# Candunio.net
KiCad netlist of a schematic drawn in Altium Designer
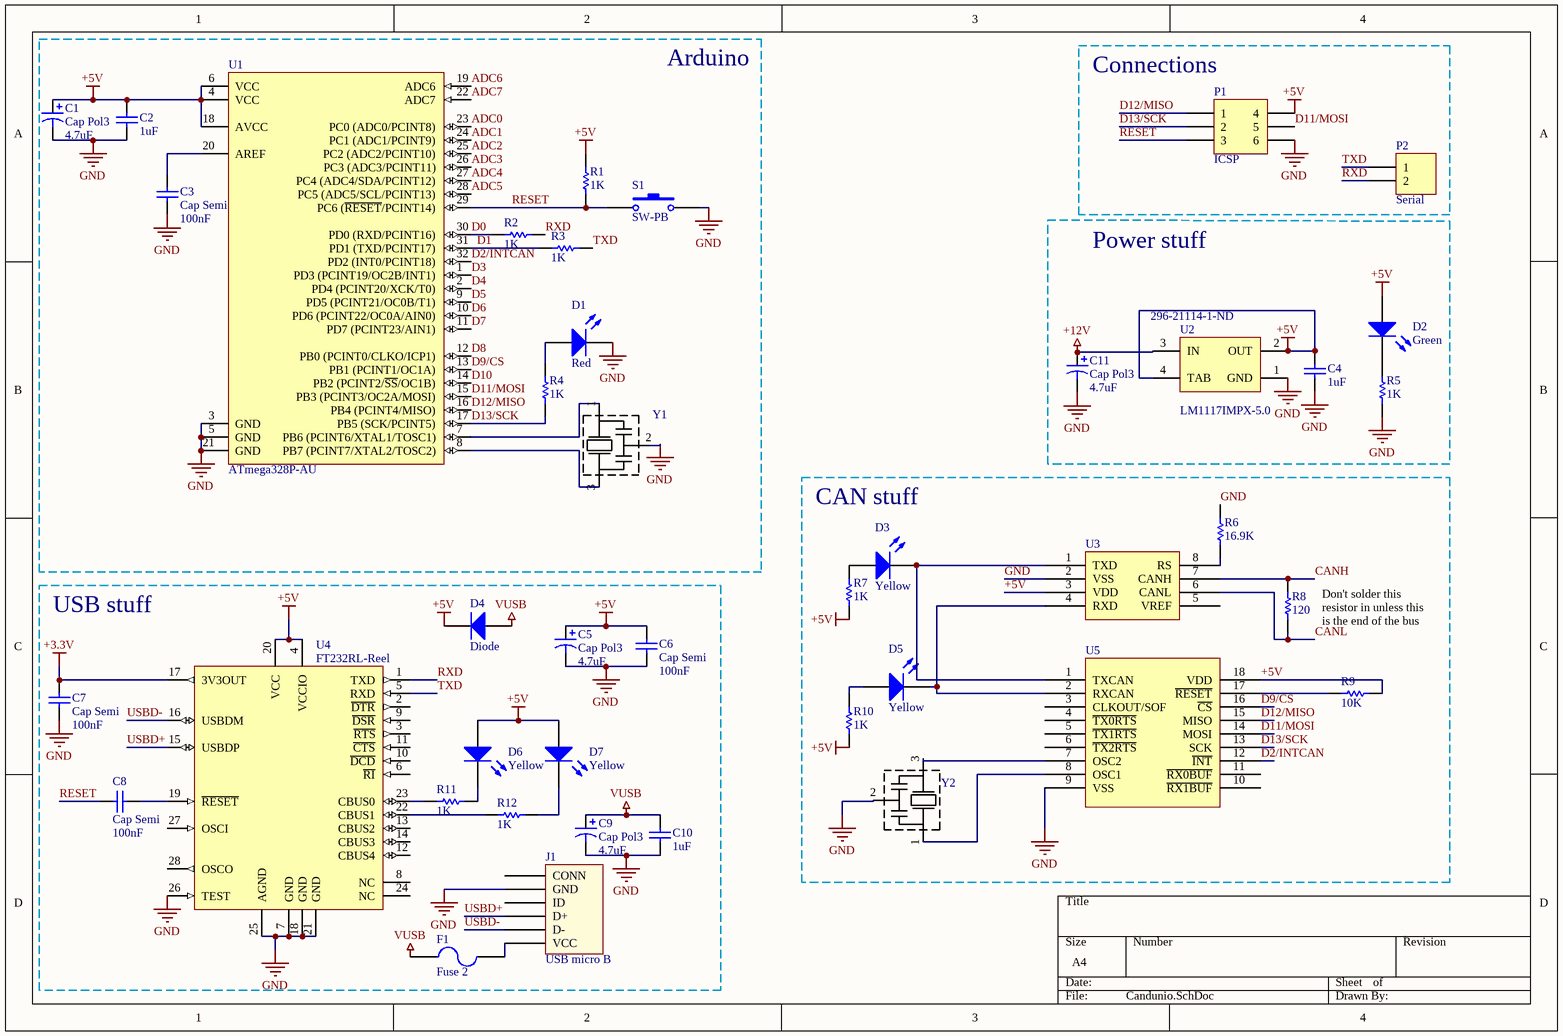
[diagram p0: Candunio.SchDoc]

(export (version "E")
  (design (tool "Eeschema 10.0.6"))
  (components
    (comp (ref "C1")
      (value "Cap Pol3")
      (footprint "C1206")
      (description "Polarized Capacitor (Surface Mount)")
      (fields
        (field (name "ALTIUM_VALUE") "4.7uF")
        (field (name "MANUFACTURER") "Kyocera AVX")
        (field (name "MANUFACTURER PART NUMBER") "12063C475KAT2A")
        (field (name "PUBLISHER") "Altium Limited")
      )
      (libsource (lib "Miscellaneous Devices") (part "Cap Pol3"))
    )
    (comp (ref "C2")
      (value "1uF")
      (footprint "C1206")
      (description "Capacitor (Semiconductor SIM Model)")
      (fields
        (field (name "MANUFACTURER") "Murata")
        (field (name "MANUFACTURER PART NUMBER") "GRM31MR71H105KA88L")
        (field (name "PUBLISHER") "Altium Limited")
      )
      (libsource (lib "Miscellaneous Devices") (part "Cap Semi"))
    )
    (comp (ref "C3")
      (value "Cap Semi")
      (footprint "C1206")
      (description "Capacitor (Semiconductor SIM Model)")
      (fields
        (field (name "ALTIUM_VALUE") "100nF")
        (field (name "MANUFACTURER") "Yageo")
        (field (name "MANUFACTURER PART NUMBER") "CC1206KKX7R0BB104")
        (field (name "PUBLISHER") "Altium Limited")
      )
      (libsource (lib "Miscellaneous Devices") (part "Cap Semi"))
    )
    (comp (ref "C4")
      (value "1uF")
      (footprint "C1206")
      (description "Capacitor (Semiconductor SIM Model)")
      (fields
        (field (name "MANUFACTURER") "Murata")
        (field (name "MANUFACTURER PART NUMBER") "GRM31MR71H105KA88L")
        (field (name "PUBLISHER") "Altium Limited")
      )
      (libsource (lib "Miscellaneous Devices") (part "Cap Semi"))
    )
    (comp (ref "C5")
      (value "Cap Pol3")
      (footprint "C1206")
      (description "Polarized Capacitor (Surface Mount)")
      (fields
        (field (name "ALTIUM_VALUE") "4.7uF")
        (field (name "MANUFACTURER") "Kyocera AVX")
        (field (name "MANUFACTURER PART NUMBER") "12063C475KAT2A")
        (field (name "PUBLISHER") "Altium Limited")
      )
      (libsource (lib "Miscellaneous Devices") (part "Cap Pol3"))
    )
    (comp (ref "C6")
      (value "Cap Semi")
      (footprint "C1206")
      (description "Capacitor (Semiconductor SIM Model)")
      (fields
        (field (name "ALTIUM_VALUE") "100nF")
        (field (name "MANUFACTURER") "Yageo")
        (field (name "MANUFACTURER PART NUMBER") "CC1206KKX7R0BB104")
        (field (name "PUBLISHER") "Altium Limited")
      )
      (libsource (lib "Miscellaneous Devices") (part "Cap Semi"))
    )
    (comp (ref "C7")
      (value "Cap Semi")
      (footprint "C1206")
      (description "Capacitor (Semiconductor SIM Model)")
      (fields
        (field (name "ALTIUM_VALUE") "100nF")
        (field (name "MANUFACTURER") "Yageo")
        (field (name "MANUFACTURER PART NUMBER") "CC1206KKX7R0BB104")
        (field (name "PUBLISHER") "Altium Limited")
      )
      (libsource (lib "Miscellaneous Devices") (part "Cap Semi"))
    )
    (comp (ref "C8")
      (value "Cap Semi")
      (footprint "C1206")
      (description "Capacitor (Semiconductor SIM Model)")
      (fields
        (field (name "ALTIUM_VALUE") "100nF")
        (field (name "MANUFACTURER") "Yageo")
        (field (name "MANUFACTURER PART NUMBER") "CC1206KKX7R0BB104")
        (field (name "PUBLISHER") "Altium Limited")
      )
      (libsource (lib "Miscellaneous Devices") (part "Cap Semi"))
    )
    (comp (ref "C9")
      (value "Cap Pol3")
      (footprint "C1206")
      (description "Polarized Capacitor (Surface Mount)")
      (fields
        (field (name "ALTIUM_VALUE") "4.7uF")
        (field (name "MANUFACTURER") "Kyocera AVX")
        (field (name "MANUFACTURER PART NUMBER") "12063C475KAT2A")
        (field (name "PUBLISHER") "Altium Limited")
      )
      (libsource (lib "Miscellaneous Devices") (part "Cap Pol3"))
    )
    (comp (ref "C10")
      (value "1uF")
      (footprint "C1206")
      (description "Capacitor (Semiconductor SIM Model)")
      (fields
        (field (name "MANUFACTURER") "Murata")
        (field (name "MANUFACTURER PART NUMBER") "GRM31MR71H105KA88L")
        (field (name "PUBLISHER") "Altium Limited")
      )
      (libsource (lib "Miscellaneous Devices") (part "Cap Semi"))
    )
    (comp (ref "C11")
      (value "Cap Pol3")
      (footprint "C1206")
      (description "Polarized Capacitor (Surface Mount)")
      (fields
        (field (name "ALTIUM_VALUE") "4.7uF")
        (field (name "MANUFACTURER") "Kyocera AVX")
        (field (name "MANUFACTURER PART NUMBER") "12063C475KAT2A")
        (field (name "PUBLISHER") "Altium Limited")
      )
      (libsource (lib "Miscellaneous Devices") (part "Cap Pol3"))
    )
    (comp (ref "D1")
      (value "Red")
      (footprint "3.2X1.6X1.1")
      (description "Typical RED, GREEN, YELLOW, AMBER GaAs LED")
      (fields
        (field (name "MANUFACTURER") "Broadcom Avago")
        (field (name "MANUFACTURER PART NUMBER") "HSMY-C150")
        (field (name "PUBLISHER") "Altium Limited")
      )
      (libsource (lib "Miscellaneous Devices") (part "LED2"))
    )
    (comp (ref "D2")
      (value "Green")
      (footprint "3.2X1.6X1.1")
      (description "Typical RED, GREEN, YELLOW, AMBER GaAs LED")
      (fields
        (field (name "MANUFACTURER") "Broadcom Avago")
        (field (name "MANUFACTURER PART NUMBER") "HSMG-C150")
        (field (name "PUBLISHER") "Altium Limited")
      )
      (libsource (lib "Miscellaneous Devices") (part "LED2"))
    )
    (comp (ref "D3")
      (value "Yellow")
      (footprint "3.2X1.6X1.1")
      (description "Typical RED, GREEN, YELLOW, AMBER GaAs LED")
      (fields
        (field (name "MANUFACTURER") "Broadcom Avago")
        (field (name "MANUFACTURER PART NUMBER") "HSMY-C150")
        (field (name "PUBLISHER") "Altium Limited")
      )
      (libsource (lib "Miscellaneous Devices") (part "LED2"))
    )
    (comp (ref "D4")
      (value "Diode")
      (footprint "SMC")
      (description "Default Diode")
      (fields (field (name "PUBLISHER") "Altium Limited"))
      (libsource (lib "Miscellaneous Devices") (part "Diode"))
    )
    (comp (ref "D5")
      (value "Yellow")
      (footprint "3.2X1.6X1.1")
      (description "Typical RED, GREEN, YELLOW, AMBER GaAs LED")
      (fields
        (field (name "MANUFACTURER") "Broadcom Avago")
        (field (name "MANUFACTURER PART NUMBER") "HSMY-C150")
        (field (name "PUBLISHER") "Altium Limited")
      )
      (libsource (lib "Miscellaneous Devices") (part "LED2"))
    )
    (comp (ref "D6")
      (value "Yellow")
      (footprint "3.2X1.6X1.1")
      (description "Typical RED, GREEN, YELLOW, AMBER GaAs LED")
      (fields
        (field (name "MANUFACTURER") "Broadcom Avago")
        (field (name "MANUFACTURER PART NUMBER") "HSMY-C150")
        (field (name "PUBLISHER") "Altium Limited")
      )
      (libsource (lib "Miscellaneous Devices") (part "LED2"))
    )
    (comp (ref "D7")
      (value "Yellow")
      (footprint "3.2X1.6X1.1")
      (description "Typical RED, GREEN, YELLOW, AMBER GaAs LED")
      (fields
        (field (name "MANUFACTURER") "Broadcom Avago")
        (field (name "MANUFACTURER PART NUMBER") "HSMY-C150")
        (field (name "PUBLISHER") "Altium Limited")
      )
      (libsource (lib "Miscellaneous Devices") (part "LED2"))
    )
    (comp (ref "F1")
      (value "Fuse 2")
      (footprint "1812")
      (description "Fuse")
      (fields
        (field (name "PART NUMBER") "MF-MSMF050-2")
        (field (name "MANUFACTURER") "Bourns")
        (field (name "PUBLISHER") "Altium Limited")
      )
      (libsource (lib "Miscellaneous Devices") (part "Fuse 2"))
    )
    (comp (ref "J1")
      (value "USB micro B")
      (footprint "1050170001")
      (description "CONN SM TH USB MICRO MODIFIED FOR DRILL")
      (fields (field (name "PART NUMBER") "WM1399CT-ND"))
      (libsource (lib "electronpowered") (part "1050170001"))
    )
    (comp (ref "P1")
      (value "ICSP")
      (footprint "HDR2X3_CEN")
      (description "Header, 3-Pin, Dual row")
      (fields (field (name "PUBLISHER") "Altium Limited"))
      (libsource (lib "Miscellaneous Connectors") (part "Header 3X2A"))
    )
    (comp (ref "P2")
      (value "Serial")
      (footprint "HDR1X2")
      (description "Header, 2-Pin")
      (fields (field (name "PUBLISHER") "Altium Limited"))
      (libsource (lib "Miscellaneous Connectors") (part "Header 2"))
    )
    (comp (ref "R1")
      (value "1K")
      (footprint "C1206")
      (description "Resistor")
      (fields
        (field (name "MANUFACTURER") "Stackpole Electronics")
        (field (name "MANUFACTURER PART NUMBER") "RNCP1206FTD1K00")
      )
      (libsource (lib "Miscellaneous Devices") (part "Res1"))
    )
    (comp (ref "R2")
      (value "1K")
      (footprint "C1206")
      (description "Resistor")
      (fields
        (field (name "MANUFACTURER") "Stackpole Electronics")
        (field (name "MANUFACTURER PART NUMBER") "RNCP1206FTD1K00")
      )
      (libsource (lib "Miscellaneous Devices") (part "Res1"))
    )
    (comp (ref "R3")
      (value "1K")
      (footprint "C1206")
      (description "Resistor")
      (fields
        (field (name "MANUFACTURER") "Stackpole Electronics")
        (field (name "MANUFACTURER PART NUMBER") "RNCP1206FTD1K00")
      )
      (libsource (lib "Miscellaneous Devices") (part "Res1"))
    )
    (comp (ref "R4")
      (value "1K")
      (footprint "C1206")
      (description "Resistor")
      (fields
        (field (name "MANUFACTURER") "Stackpole Electronics")
        (field (name "MANUFACTURER PART NUMBER") "RNCP1206FTD1K00")
      )
      (libsource (lib "Miscellaneous Devices") (part "Res1"))
    )
    (comp (ref "R5")
      (value "1K")
      (footprint "C1206")
      (description "Resistor")
      (fields
        (field (name "MANUFACTURER") "Stackpole Electronics")
        (field (name "MANUFACTURER PART NUMBER") "RNCP1206FTD1K00")
      )
      (libsource (lib "Miscellaneous Devices") (part "Res1"))
    )
    (comp (ref "R6")
      (value "16.9K")
      (footprint "C1206")
      (description "Resistor")
      (fields
        (field (name "MANUFACTURER") "TE Connectivity Holsworthy")
        (field (name "MANUFACTURER PART NUMBER") "CRGH1206F16K9")
      )
      (libsource (lib "Miscellaneous Devices") (part "Res1"))
    )
    (comp (ref "R7")
      (value "1K")
      (footprint "C1206")
      (description "Resistor")
      (fields
        (field (name "MANUFACTURER") "Stackpole Electronics")
        (field (name "MANUFACTURER PART NUMBER") "RNCP1206FTD1K00")
      )
      (libsource (lib "Miscellaneous Devices") (part "Res1"))
    )
    (comp (ref "R8")
      (value "120")
      (footprint "C1206")
      (description "Resistor")
      (fields
        (field (name "MANUFACTURER") "Vishay")
        (field (name "MANUFACTURER PART NUMBER") "CRCW1206120RFKEAHP")
      )
      (libsource (lib "Miscellaneous Devices") (part "Res1"))
    )
    (comp (ref "R9")
      (value "10K")
      (footprint "C1206")
      (description "Resistor")
      (fields
        (field (name "MANUFACTURER") "Stackpole Electronics")
        (field (name "MANUFACTURER PART NUMBER") "RNCP1206FTD10K0")
      )
      (libsource (lib "Miscellaneous Devices") (part "Res1"))
    )
    (comp (ref "R10")
      (value "1K")
      (footprint "C1206")
      (description "Resistor")
      (fields
        (field (name "MANUFACTURER") "Stackpole Electronics")
        (field (name "MANUFACTURER PART NUMBER") "RNCP1206FTD1K00")
      )
      (libsource (lib "Miscellaneous Devices") (part "Res1"))
    )
    (comp (ref "R11")
      (value "1K")
      (footprint "C1206")
      (description "Resistor")
      (fields
        (field (name "MANUFACTURER") "Stackpole Electronics")
        (field (name "MANUFACTURER PART NUMBER") "RNCP1206FTD1K00")
      )
      (libsource (lib "Miscellaneous Devices") (part "Res1"))
    )
    (comp (ref "R12")
      (value "1K")
      (footprint "C1206")
      (description "Resistor")
      (fields
        (field (name "MANUFACTURER") "Stackpole Electronics")
        (field (name "MANUFACTURER PART NUMBER") "RNCP1206FTD1K00")
      )
      (libsource (lib "Miscellaneous Devices") (part "Res1"))
    )
    (comp (ref "S1")
      (value "SW-PB")
      (footprint "C1206")
      (description "Switch")
      (fields
        (field (name "MANUFACTURER") "ITT C&K")
        (field (name "MANUFACTURER PART NUMBER") "KXT331LHS")
        (field (name "PUBLISHER") "Altium Limited")
      )
      (libsource (lib "Miscellaneous Devices") (part "SW-PB"))
    )
    (comp (ref "U1")
      (value "ATmega328P-AU")
      (footprint "32A_N")
      (fields (field (name "PUBLISHER") "Altium Limited"))
      (libsource (lib "Atmel Microcontroller 8-Bit megaAVR") (part "ATmega328P-AU"))
    )
    (comp (ref "U2")
      (value "LM1117IMPX-5.0")
      (footprint "MP04A_N")
      (description "800mA Low-Dropout Linear Regulator, 4-pin SOT-223")
      (fields
        (field (name "PARTNUMBER") "LM1117IMPX-5.0/NOPBCT-ND")
        (field (name "MANUFACTURER") "National Semiconductor")
        (field (name "SUPPLIER PART NUMBER") "296-21114-1-ND")
        (field (name "PUBLISHER") "Altium Limited")
      )
      (libsource (lib "NSC LDO") (part "LM1117IMPX-5.0"))
    )
    (comp (ref "U3")
      (value "MCP2551-E/SN")
      (footprint "SOIC127P600X175-8M")
      (description "SOIC")
      (libsource (lib "AMSComponents") (part "MCP2551-E/SN"))
    )
    (comp (ref "U4")
      (value "FT232RL-Reel")
      (footprint "SSOP-28_N")
      (description "USB UART Asynchronous Serial Data Transfer Chip, SSOP-28, Tape and Reel")
      (fields
        (field (name "MANUFACTURER") "FTDI")
        (field (name "MANUFACTURER PART NUMBER") "FT232RL-REEL")
        (field (name "PUBLISHER") "Altium Limited")
      )
      (libsource (lib "FTDI Communication UART") (part "FT232RL-Reel"))
    )
    (comp (ref "U5")
      (value "MCP2515-E/ST")
      (footprint "SOIC127P1030X265-18M")
      (description "SOIC")
      (libsource (lib "AMSComponents") (part "MCP2515-E/ST"))
    )
    (comp (ref "Y1")
      (value "CSTCE16M0V53-R0")
      (footprint "CSTCE16M0V53-R0")
      (fields
        (field (name "MANUFACTURER") "Murata")
        (field (name "MANUFACTURER PART NUMBER") "CSTCE16M0V53C-R0")
        (field (name "TOLERANCE") "0.5%")
      )
      (libsource (lib "AMSComponents") (part "CSTCE16M0V53-R0"))
    )
    (comp (ref "Y2")
      (value "CSTCE16M0V53-R0")
      (footprint "CSTCE16M0V53-R0")
      (fields
        (field (name "MANUFACTURER") "Murata")
        (field (name "MANUFACTURER PART NUMBER") "CSTCE16M0V53C-R0")
        (field (name "TOLERANCE") "0.5%")
      )
      (libsource (lib "AMSComponents") (part "CSTCE16M0V53-R0"))
    )
  )
  (nets
    (net (code "1") (name "+3.3V") (class "Default")
      (node (ref "C7") (pin "1") (pinfunction "1_1") (pintype "passive"))
      (node (ref "U4") (pin "17") (pinfunction "3V3OUT_17") (pintype "output"))
    )
    (net (code "2") (name "+5V") (class "Default")
      (node (ref "C1") (pin "1") (pinfunction "1_1") (pintype "passive"))
      (node (ref "C2") (pin "1") (pinfunction "1_1") (pintype "passive"))
      (node (ref "C4") (pin "1") (pinfunction "1_1") (pintype "passive"))
      (node (ref "C5") (pin "1") (pinfunction "1_1") (pintype "passive"))
      (node (ref "C6") (pin "1") (pinfunction "1_1") (pintype "passive"))
      (node (ref "D2") (pin "1") (pinfunction "A_1") (pintype "passive"))
      (node (ref "D4") (pin "2") (pinfunction "K_2") (pintype "passive"))
      (node (ref "D6") (pin "1") (pinfunction "A_1") (pintype "passive"))
      (node (ref "D7") (pin "1") (pinfunction "A_1") (pintype "passive"))
      (node (ref "P1") (pin "4") (pinfunction "4_4") (pintype "passive"))
      (node (ref "R1") (pin "1") (pinfunction "1_1") (pintype "passive"))
      (node (ref "R10") (pin "2") (pinfunction "2_2") (pintype "passive"))
      (node (ref "R7") (pin "1") (pinfunction "1_1") (pintype "passive"))
      (node (ref "R9") (pin "2") (pinfunction "2_2") (pintype "passive"))
      (node (ref "U1") (pin "18") (pinfunction "AVCC_18") (pintype "power_in"))
      (node (ref "U1") (pin "4") (pinfunction "VCC_4") (pintype "power_in"))
      (node (ref "U1") (pin "6") (pinfunction "VCC_6") (pintype "power_in"))
      (node (ref "U2") (pin "2") (pinfunction "OUT_2") (pintype "power_in"))
      (node (ref "U2") (pin "4") (pinfunction "TAB_4") (pintype "power_in"))
      (node (ref "U3") (pin "3") (pinfunction "VDD_3") (pintype "passive"))
      (node (ref "U4") (pin "20") (pinfunction "VCC_20") (pintype "power_in"))
      (node (ref "U4") (pin "4") (pinfunction "VCCIO_4") (pintype "power_in"))
      (node (ref "U5") (pin "18") (pinfunction "VDD_18") (pintype "passive"))
    )
    (net (code "3") (name "+12V") (class "Default")
      (node (ref "C11") (pin "1") (pinfunction "1_1") (pintype "passive"))
      (node (ref "U2") (pin "3") (pinfunction "IN_3") (pintype "power_in"))
    )
    (net (code "4") (name "/ADC0") (class "Default")
      (node (ref "U1") (pin "23") (pinfunction "PC0_(ADC0/PCINT8)_23") (pintype "bidirectional"))
    )
    (net (code "5") (name "/ADC1") (class "Default")
      (node (ref "U1") (pin "24") (pinfunction "PC1_(ADC1/PCINT9)_24") (pintype "bidirectional"))
    )
    (net (code "6") (name "/ADC2") (class "Default")
      (node (ref "U1") (pin "25") (pinfunction "PC2_(ADC2/PCINT10)_25") (pintype "bidirectional"))
    )
    (net (code "7") (name "/ADC3") (class "Default")
      (node (ref "U1") (pin "26") (pinfunction "PC3_(ADC3/PCINT11)_26") (pintype "bidirectional"))
    )
    (net (code "8") (name "/ADC4") (class "Default")
      (node (ref "U1") (pin "27") (pinfunction "PC4_(ADC4/SDA/PCINT12)_27") (pintype "bidirectional"))
    )
    (net (code "9") (name "/ADC5") (class "Default")
      (node (ref "U1") (pin "28") (pinfunction "PC5_(ADC5/SCL/PCINT13)_28") (pintype "bidirectional"))
    )
    (net (code "10") (name "/ADC6") (class "Default")
      (node (ref "U1") (pin "19") (pinfunction "ADC6_19") (pintype "input"))
    )
    (net (code "11") (name "/ADC7") (class "Default")
      (node (ref "U1") (pin "22") (pinfunction "ADC7_22") (pintype "input"))
    )
    (net (code "12") (name "/CANH") (class "Default")
      (node (ref "R8") (pin "1") (pinfunction "1_1") (pintype "passive"))
      (node (ref "U3") (pin "7") (pinfunction "CANH_7") (pintype "passive"))
    )
    (net (code "13") (name "/CANL") (class "Default")
      (node (ref "R8") (pin "2") (pinfunction "2_2") (pintype "passive"))
      (node (ref "U3") (pin "6") (pinfunction "CANL_6") (pintype "passive"))
    )
    (net (code "14") (name "/D0") (class "Default")
      (node (ref "R2") (pin "1") (pinfunction "1_1") (pintype "passive"))
      (node (ref "U1") (pin "30") (pinfunction "PD0_(RXD/PCINT16)_30") (pintype "bidirectional"))
    )
    (net (code "15") (name "/D1") (class "Default")
      (node (ref "R3") (pin "1") (pinfunction "1_1") (pintype "passive"))
      (node (ref "U1") (pin "31") (pinfunction "PD1_(TXD/PCINT17)_31") (pintype "bidirectional"))
    )
    (net (code "16") (name "/D2{slash}INTCAN") (class "Default")
      (node (ref "U1") (pin "32") (pinfunction "PD2_(INT0/PCINT18)_32") (pintype "bidirectional"))
      (node (ref "U5") (pin "12") (pinfunction "~{INT}_12") (pintype "passive"))
    )
    (net (code "17") (name "/D3") (class "Default")
      (node (ref "U1") (pin "1") (pinfunction "PD3_(PCINT19/OC2B/INT1)_1") (pintype "bidirectional"))
    )
    (net (code "18") (name "/D4") (class "Default")
      (node (ref "U1") (pin "2") (pinfunction "PD4_(PCINT20/XCK/T0)_2") (pintype "bidirectional"))
    )
    (net (code "19") (name "/D5") (class "Default")
      (node (ref "U1") (pin "9") (pinfunction "PD5_(PCINT21/OC0B/T1)_9") (pintype "bidirectional"))
    )
    (net (code "20") (name "/D6") (class "Default")
      (node (ref "U1") (pin "10") (pinfunction "PD6_(PCINT22/OC0A/AIN0)_10") (pintype "bidirectional"))
    )
    (net (code "21") (name "/D7") (class "Default")
      (node (ref "U1") (pin "11") (pinfunction "PD7_(PCINT23/AIN1)_11") (pintype "bidirectional"))
    )
    (net (code "22") (name "/D8") (class "Default")
      (node (ref "U1") (pin "12") (pinfunction "PB0_(PCINT0/CLKO/ICP1)_12") (pintype "bidirectional"))
    )
    (net (code "23") (name "/D9{slash}CS") (class "Default")
      (node (ref "U1") (pin "13") (pinfunction "PB1_(PCINT1/OC1A)_13") (pintype "bidirectional"))
      (node (ref "U5") (pin "16") (pinfunction "~{CS}_16") (pintype "passive"))
    )
    (net (code "24") (name "/D10") (class "Default")
      (node (ref "U1") (pin "14") (pinfunction "PB2_(PCINT2/~{SS}/OC1B)_14") (pintype "bidirectional"))
    )
    (net (code "25") (name "/D11{slash}MOSI") (class "Default")
      (node (ref "P1") (pin "5") (pinfunction "5_5") (pintype "passive"))
      (node (ref "U1") (pin "15") (pinfunction "PB3_(PCINT3/OC2A/MOSI)_15") (pintype "bidirectional"))
      (node (ref "U5") (pin "14") (pinfunction "MOSI_14") (pintype "passive"))
    )
    (net (code "26") (name "/D12{slash}MISO") (class "Default")
      (node (ref "P1") (pin "1") (pinfunction "1_1") (pintype "passive"))
      (node (ref "U1") (pin "16") (pinfunction "PB4_(PCINT4/MISO)_16") (pintype "bidirectional"))
      (node (ref "U5") (pin "15") (pinfunction "MISO_15") (pintype "passive"))
    )
    (net (code "27") (name "/D13{slash}SCK") (class "Default")
      (node (ref "P1") (pin "2") (pinfunction "2_2") (pintype "passive"))
      (node (ref "R4") (pin "2") (pinfunction "2_2") (pintype "passive"))
      (node (ref "U1") (pin "17") (pinfunction "PB5_(SCK/PCINT5)_17") (pintype "bidirectional"))
      (node (ref "U5") (pin "13") (pinfunction "SCK_13") (pintype "passive"))
    )
    (net (code "28") (name "/RESET") (class "Default")
      (node (ref "C8") (pin "1") (pinfunction "1_1") (pintype "passive"))
      (node (ref "P1") (pin "3") (pinfunction "3_3") (pintype "passive"))
      (node (ref "R1") (pin "2") (pinfunction "2_2") (pintype "passive"))
      (node (ref "S1") (pin "1") (pinfunction "1_1") (pintype "passive"))
      (node (ref "U1") (pin "29") (pinfunction "PC6_(~{RESET}/PCINT14)_29") (pintype "bidirectional"))
    )
    (net (code "29") (name "/RXD") (class "Default")
      (node (ref "P2") (pin "2") (pinfunction "2_2") (pintype "passive"))
      (node (ref "R2") (pin "2") (pinfunction "2_2") (pintype "passive"))
      (node (ref "U4") (pin "1") (pinfunction "TXD_1") (pintype "output"))
    )
    (net (code "30") (name "/TXD") (class "Default")
      (node (ref "P2") (pin "1") (pinfunction "1_1") (pintype "passive"))
      (node (ref "R3") (pin "2") (pinfunction "2_2") (pintype "passive"))
      (node (ref "U4") (pin "5") (pinfunction "RXD_5") (pintype "input"))
    )
    (net (code "31") (name "/USBD+") (class "Default")
      (node (ref "J1") (pin "3") (pinfunction "D+_3") (pintype "passive"))
      (node (ref "U4") (pin "15") (pinfunction "USBDP_15") (pintype "bidirectional"))
    )
    (net (code "32") (name "/USBD-") (class "Default")
      (node (ref "J1") (pin "2") (pinfunction "D-_2") (pintype "passive"))
      (node (ref "U4") (pin "16") (pinfunction "USBDM_16") (pintype "bidirectional"))
    )
    (net (code "33") (name "GND") (class "Default")
      (node (ref "C1") (pin "2") (pinfunction "2_2") (pintype "passive"))
      (node (ref "C10") (pin "2") (pinfunction "2_2") (pintype "passive"))
      (node (ref "C11") (pin "2") (pinfunction "2_2") (pintype "passive"))
      (node (ref "C2") (pin "2") (pinfunction "2_2") (pintype "passive"))
      (node (ref "C3") (pin "2") (pinfunction "2_2") (pintype "passive"))
      (node (ref "C4") (pin "2") (pinfunction "2_2") (pintype "passive"))
      (node (ref "C5") (pin "2") (pinfunction "2_2") (pintype "passive"))
      (node (ref "C6") (pin "2") (pinfunction "2_2") (pintype "passive"))
      (node (ref "C7") (pin "2") (pinfunction "2_2") (pintype "passive"))
      (node (ref "C9") (pin "2") (pinfunction "2_2") (pintype "passive"))
      (node (ref "D1") (pin "2") (pinfunction "K_2") (pintype "passive"))
      (node (ref "J1") (pin "5") (pinfunction "GND_5") (pintype "passive"))
      (node (ref "P1") (pin "6") (pinfunction "6_6") (pintype "passive"))
      (node (ref "R5") (pin "2") (pinfunction "2_2") (pintype "passive"))
      (node (ref "R6") (pin "1") (pinfunction "1_1") (pintype "passive"))
      (node (ref "S1") (pin "2") (pinfunction "2_2") (pintype "passive"))
      (node (ref "U1") (pin "21") (pinfunction "GND_21") (pintype "power_in"))
      (node (ref "U1") (pin "3") (pinfunction "GND_3") (pintype "power_in"))
      (node (ref "U1") (pin "5") (pinfunction "GND_5") (pintype "power_in"))
      (node (ref "U2") (pin "1") (pinfunction "GND_1") (pintype "power_in"))
      (node (ref "U3") (pin "2") (pinfunction "VSS_2") (pintype "passive"))
      (node (ref "U4") (pin "18") (pinfunction "GND_18") (pintype "power_in"))
      (node (ref "U4") (pin "21") (pinfunction "GND_21") (pintype "power_in"))
      (node (ref "U4") (pin "25") (pinfunction "AGND_25") (pintype "power_in"))
      (node (ref "U4") (pin "26") (pinfunction "TEST_26") (pintype "input"))
      (node (ref "U4") (pin "7") (pinfunction "GND_7") (pintype "power_in"))
      (node (ref "U5") (pin "9") (pinfunction "VSS_9") (pintype "passive"))
      (node (ref "Y1") (pin "2") (pinfunction "2_2") (pintype "passive"))
      (node (ref "Y2") (pin "2") (pinfunction "2_2") (pintype "passive"))
    )
    (net (code "34") (name "Net-(D1-A)") (class "Default")
      (node (ref "D1") (pin "1") (pinfunction "A_1") (pintype "passive"))
      (node (ref "R4") (pin "1") (pinfunction "1_1") (pintype "passive"))
    )
    (net (code "35") (name "Net-(D2-K)") (class "Default")
      (node (ref "D2") (pin "2") (pinfunction "K_2") (pintype "passive"))
      (node (ref "R5") (pin "1") (pinfunction "1_1") (pintype "passive"))
    )
    (net (code "36") (name "Net-(D3-A)") (class "Default")
      (node (ref "D3") (pin "1") (pinfunction "A_1") (pintype "passive"))
      (node (ref "R7") (pin "2") (pinfunction "2_2") (pintype "passive"))
    )
    (net (code "37") (name "Net-(D3-K)") (class "Default")
      (node (ref "D3") (pin "2") (pinfunction "K_2") (pintype "passive"))
      (node (ref "U3") (pin "1") (pinfunction "TXD_1") (pintype "passive"))
      (node (ref "U5") (pin "1") (pinfunction "TXCAN_1") (pintype "passive"))
    )
    (net (code "38") (name "Net-(D5-A)") (class "Default")
      (node (ref "D5") (pin "1") (pinfunction "A_1") (pintype "passive"))
      (node (ref "R10") (pin "1") (pinfunction "1_1") (pintype "passive"))
    )
    (net (code "39") (name "Net-(D5-K)") (class "Default")
      (node (ref "D5") (pin "2") (pinfunction "K_2") (pintype "passive"))
      (node (ref "U3") (pin "4") (pinfunction "RXD_4") (pintype "passive"))
      (node (ref "U5") (pin "2") (pinfunction "RXCAN_2") (pintype "passive"))
    )
    (net (code "40") (name "Net-(D6-K)") (class "Default")
      (node (ref "D6") (pin "2") (pinfunction "K_2") (pintype "passive"))
      (node (ref "R11") (pin "2") (pinfunction "2_2") (pintype "passive"))
    )
    (net (code "41") (name "Net-(D7-K)") (class "Default")
      (node (ref "D7") (pin "2") (pinfunction "K_2") (pintype "passive"))
      (node (ref "R12") (pin "2") (pinfunction "2_2") (pintype "passive"))
    )
    (net (code "42") (name "Net-(J1-VCC)") (class "Default")
      (node (ref "F1") (pin "2") (pinfunction "2_2") (pintype "passive"))
      (node (ref "J1") (pin "1") (pinfunction "VCC_1") (pintype "passive"))
    )
    (net (code "43") (name "Net-(U1-AREF)") (class "Default")
      (node (ref "C3") (pin "1") (pinfunction "1_1") (pintype "passive"))
      (node (ref "U1") (pin "20") (pinfunction "AREF_20") (pintype "passive"))
    )
    (net (code "44") (name "Net-(U1-PB6_(PCINT6{slash}XTAL1{slash}TOSC1))") (class "Default")
      (node (ref "U1") (pin "7") (pinfunction "PB6_(PCINT6/XTAL1/TOSC1)_7") (pintype "bidirectional"))
      (node (ref "Y1") (pin "1") (pinfunction "1_1") (pintype "passive"))
    )
    (net (code "45") (name "Net-(U1-PB7_(PCINT7{slash}XTAL2{slash}TOSC2))") (class "Default")
      (node (ref "U1") (pin "8") (pinfunction "PB7_(PCINT7/XTAL2/TOSC2)_8") (pintype "bidirectional"))
      (node (ref "Y1") (pin "3") (pinfunction "3_3") (pintype "passive"))
    )
    (net (code "46") (name "Net-(U3-RS)") (class "Default")
      (node (ref "R6") (pin "2") (pinfunction "2_2") (pintype "passive"))
      (node (ref "U3") (pin "8") (pinfunction "RS_8") (pintype "passive"))
    )
    (net (code "47") (name "Net-(U4-CBUS0)") (class "Default")
      (node (ref "R11") (pin "1") (pinfunction "1_1") (pintype "passive"))
      (node (ref "U4") (pin "23") (pinfunction "CBUS0_23") (pintype "bidirectional"))
    )
    (net (code "48") (name "Net-(U4-CBUS1)") (class "Default")
      (node (ref "R12") (pin "1") (pinfunction "1_1") (pintype "passive"))
      (node (ref "U4") (pin "22") (pinfunction "CBUS1_22") (pintype "bidirectional"))
    )
    (net (code "49") (name "Net-(U4-~{RESET})") (class "Default")
      (node (ref "C8") (pin "2") (pinfunction "2_2") (pintype "passive"))
      (node (ref "U4") (pin "19") (pinfunction "~{RESET}_19") (pintype "input"))
    )
    (net (code "50") (name "Net-(U5-OSC1)") (class "Default")
      (node (ref "U5") (pin "8") (pinfunction "OSC1_8") (pintype "passive"))
      (node (ref "Y2") (pin "1") (pinfunction "1_1") (pintype "passive"))
    )
    (net (code "51") (name "Net-(U5-OSC2)") (class "Default")
      (node (ref "U5") (pin "7") (pinfunction "OSC2_7") (pintype "passive"))
      (node (ref "Y2") (pin "3") (pinfunction "3_3") (pintype "passive"))
    )
    (net (code "52") (name "Net-(U5-~{RESET})") (class "Default")
      (node (ref "R9") (pin "1") (pinfunction "1_1") (pintype "passive"))
      (node (ref "U5") (pin "17") (pinfunction "~{RESET}_17") (pintype "passive"))
    )
    (net (code "53") (name "VUSB") (class "Default")
      (node (ref "C10") (pin "1") (pinfunction "1_1") (pintype "passive"))
      (node (ref "C9") (pin "1") (pinfunction "1_1") (pintype "passive"))
      (node (ref "D4") (pin "1") (pinfunction "A_1") (pintype "passive"))
      (node (ref "F1") (pin "1") (pinfunction "1_1") (pintype "passive"))
    )
    (net (code "54") (name "unconnected-(J1-CONN-Pad0)") (class "Default")
      (node (ref "J1") (pin "0") (pinfunction "CONN_0") (pintype "passive"))
    )
    (net (code "55") (name "unconnected-(J1-ID-Pad4)") (class "Default")
      (node (ref "J1") (pin "4") (pinfunction "ID_4") (pintype "passive"))
    )
    (net (code "56") (name "unconnected-(U3-VREF-Pad5)") (class "Default")
      (node (ref "U3") (pin "5") (pinfunction "VREF_5") (pintype "passive"))
    )
    (net (code "57") (name "unconnected-(U4-CBUS2-Pad13)") (class "Default")
      (node (ref "U4") (pin "13") (pinfunction "CBUS2_13") (pintype "bidirectional"))
    )
    (net (code "58") (name "unconnected-(U4-CBUS3-Pad14)") (class "Default")
      (node (ref "U4") (pin "14") (pinfunction "CBUS3_14") (pintype "bidirectional"))
    )
    (net (code "59") (name "unconnected-(U4-CBUS4-Pad12)") (class "Default")
      (node (ref "U4") (pin "12") (pinfunction "CBUS4_12") (pintype "bidirectional"))
    )
    (net (code "60") (name "unconnected-(U4-NC-Pad8)") (class "Default")
      (node (ref "U4") (pin "8") (pinfunction "NC_8") (pintype "passive"))
    )
    (net (code "61") (name "unconnected-(U4-NC-Pad24)") (class "Default")
      (node (ref "U4") (pin "24") (pinfunction "NC_24") (pintype "passive"))
    )
    (net (code "62") (name "unconnected-(U4-OSCI-Pad27)") (class "Default")
      (node (ref "U4") (pin "27") (pinfunction "OSCI_27") (pintype "input"))
    )
    (net (code "63") (name "unconnected-(U4-OSCO-Pad28)") (class "Default")
      (node (ref "U4") (pin "28") (pinfunction "OSCO_28") (pintype "output"))
    )
    (net (code "64") (name "unconnected-(U4-~{CTS}-Pad11)") (class "Default")
      (node (ref "U4") (pin "11") (pinfunction "~{CTS}_11") (pintype "input"))
    )
    (net (code "65") (name "unconnected-(U4-~{DCD}-Pad10)") (class "Default")
      (node (ref "U4") (pin "10") (pinfunction "~{DCD}_10") (pintype "input"))
    )
    (net (code "66") (name "unconnected-(U4-~{DSR}-Pad9)") (class "Default")
      (node (ref "U4") (pin "9") (pinfunction "~{DSR}_9") (pintype "input"))
    )
    (net (code "67") (name "unconnected-(U4-~{DTR}-Pad2)") (class "Default")
      (node (ref "U4") (pin "2") (pinfunction "~{DTR}_2") (pintype "output"))
    )
    (net (code "68") (name "unconnected-(U4-~{RI}-Pad6)") (class "Default")
      (node (ref "U4") (pin "6") (pinfunction "~{RI}_6") (pintype "input"))
    )
    (net (code "69") (name "unconnected-(U4-~{RTS}-Pad3)") (class "Default")
      (node (ref "U4") (pin "3") (pinfunction "~{RTS}_3") (pintype "output"))
    )
    (net (code "70") (name "unconnected-(U5-CLKOUT{slash}SOF-Pad3)") (class "Default")
      (node (ref "U5") (pin "3") (pinfunction "CLKOUT/SOF_3") (pintype "passive"))
    )
    (net (code "71") (name "unconnected-(U5-~{RX0BUF}-Pad11)") (class "Default")
      (node (ref "U5") (pin "11") (pinfunction "~{RX0BUF}_11") (pintype "passive"))
    )
    (net (code "72") (name "unconnected-(U5-~{RX1BUF}-Pad10)") (class "Default")
      (node (ref "U5") (pin "10") (pinfunction "~{RX1BUF}_10") (pintype "passive"))
    )
    (net (code "73") (name "unconnected-(U5-~{TX0RTS}-Pad4)") (class "Default")
      (node (ref "U5") (pin "4") (pinfunction "~{TX0RTS}_4") (pintype "passive"))
    )
    (net (code "74") (name "unconnected-(U5-~{TX1RTS}-Pad5)") (class "Default")
      (node (ref "U5") (pin "5") (pinfunction "~{TX1RTS}_5") (pintype "passive"))
    )
    (net (code "75") (name "unconnected-(U5-~{TX2RTS}-Pad6)") (class "Default")
      (node (ref "U5") (pin "6") (pinfunction "~{TX2RTS}_6") (pintype "passive"))
    )
  )
)
